# LoadCellAmplifier.net
KiCad netlist of a schematic drawn in Altium Designer
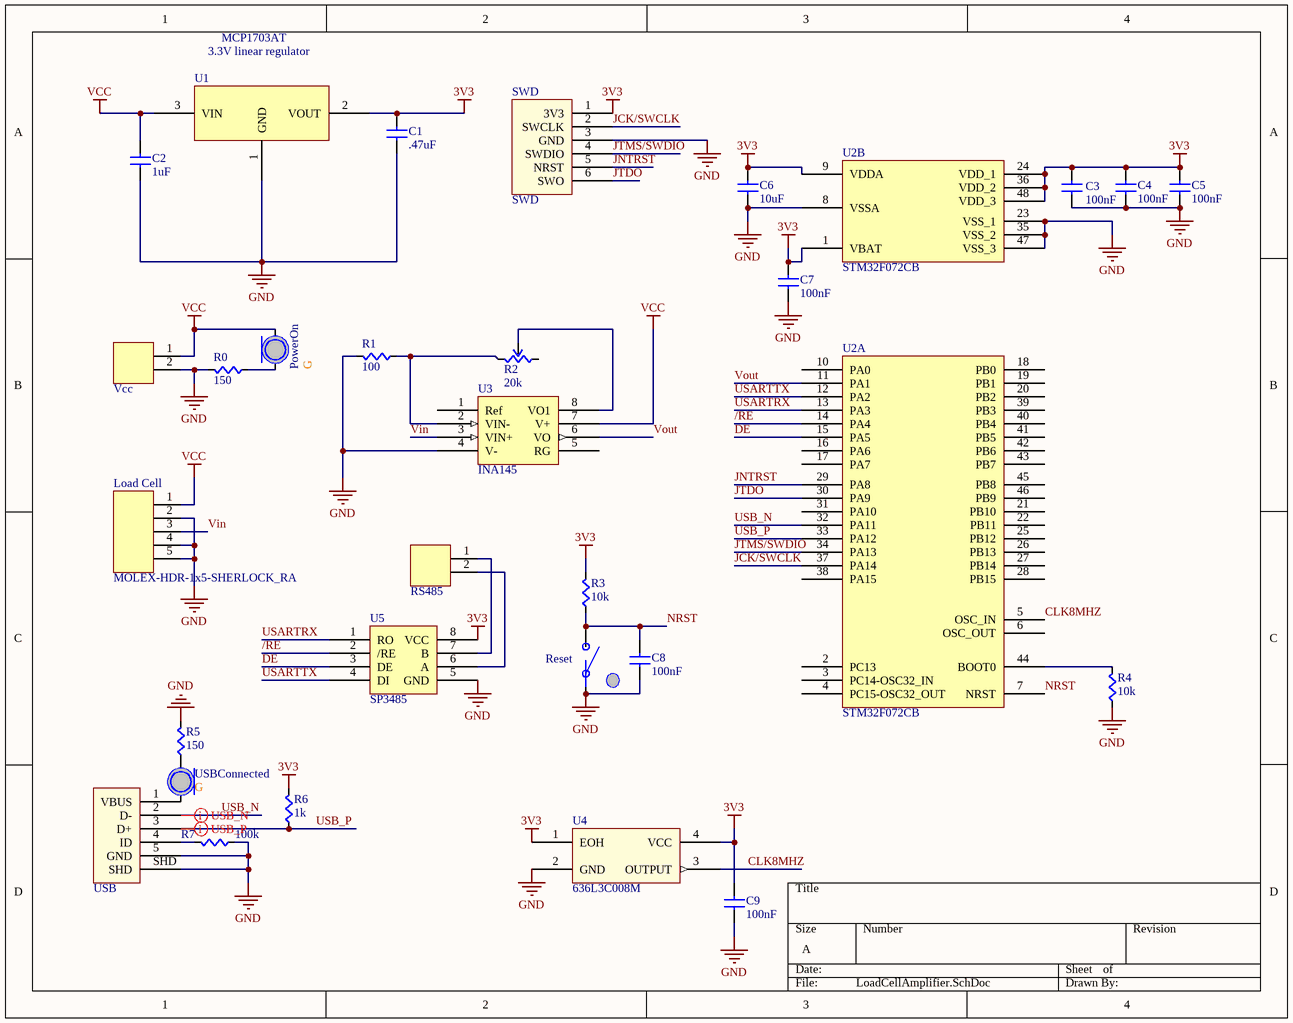
[diagram p0: LoadCellAmplifier.SchDoc]

(export (version "E")
  (design (tool "Eeschema 10.0.6"))
  (components
    (comp (ref "C1")
      (value ".47uF")
      (footprint "CAPC0603")
      (fields (field (name "Comment") "Cap"))
      (libsource (lib "SubjuGator8") (part "Cap"))
    )
    (comp (ref "C2")
      (value "1uF")
      (footprint "CAPC0603")
      (fields (field (name "Comment") "Cap"))
      (libsource (lib "SubjuGator8") (part "Cap"))
    )
    (comp (ref "C3")
      (value "100nF")
      (footprint "CAPC0603")
      (fields (field (name "Comment") "Cap"))
      (libsource (lib "SubjuGator8") (part "Cap"))
    )
    (comp (ref "C4")
      (value "100nF")
      (footprint "CAPC0603")
      (fields (field (name "Comment") "Cap"))
      (libsource (lib "SubjuGator8") (part "Cap"))
    )
    (comp (ref "C5")
      (value "100nF")
      (footprint "CAPC0603")
      (fields (field (name "Comment") "Cap"))
      (libsource (lib "SubjuGator8") (part "Cap"))
    )
    (comp (ref "C6")
      (value "10uF")
      (footprint "CAPC1206")
      (fields (field (name "Comment") "Cap"))
      (libsource (lib "SubjuGator8") (part "Cap"))
    )
    (comp (ref "C7")
      (value "100nF")
      (footprint "CAPC0603")
      (fields (field (name "Comment") "Cap"))
      (libsource (lib "SubjuGator8") (part "Cap"))
    )
    (comp (ref "C8")
      (value "100nF")
      (footprint "CAPC0603")
      (fields (field (name "Comment") "Cap"))
      (libsource (lib "SubjuGator8") (part "Cap"))
    )
    (comp (ref "C9")
      (value "100nF")
      (footprint "CAPC0603")
      (fields (field (name "Comment") "Cap"))
      (libsource (lib "SubjuGator8") (part "Cap"))
    )
    (comp (ref "Load Cell")
      (value "MOLEX-HDR-1x5-SHERLOCK_RA")
      (footprint "MOLEX-HDR-1X5-SHERLOCK- RA")
      (fields (field (name "MANUFACTURER PART NUMBER") "0353630560") (field (name "MANUFACTURER") "Molex"))
      (libsource (lib "Connectors") (part "MOLEX-HDR-1x5-SHERLOCK_RA"))
    )
    (comp (ref "PowerOn")
      (value "LED")
      (footprint "LED0805")
      (fields (field (name "COLOR") "G"))
      (libsource (lib "SubjuGator8") (part "LED"))
    )
    (comp (ref "R0")
      (value "150")
      (footprint "RES0603")
      (fields (field (name "Comment") "Res"))
      (libsource (lib "SubjuGator8") (part "Res"))
    )
    (comp (ref "R1")
      (value "100")
      (footprint "RES0603")
      (fields (field (name "Comment") "Res"))
      (libsource (lib "SubjuGator8") (part "Res"))
    )
    (comp (ref "R2")
      (value "20k")
      (footprint "ST4ETA103")
      (description "Potentiometer")
      (fields (field (name "Comment") "Pot"))
      (libsource (lib "SubjuGator8") (part "Potentiometer"))
    )
    (comp (ref "R3")
      (value "10k")
      (footprint "RES0603")
      (fields (field (name "Comment") "Res"))
      (libsource (lib "SubjuGator8") (part "Res"))
    )
    (comp (ref "R4")
      (value "10k")
      (footprint "RES0603")
      (fields (field (name "Comment") "Res"))
      (libsource (lib "SubjuGator8") (part "Res"))
    )
    (comp (ref "R5")
      (value "150")
      (footprint "RES0603")
      (fields (field (name "Comment") "Res"))
      (libsource (lib "SubjuGator8") (part "Res"))
    )
    (comp (ref "R6")
      (value "1k")
      (footprint "RES0603")
      (fields (field (name "Comment") "Res"))
      (libsource (lib "SubjuGator8") (part "Res"))
    )
    (comp (ref "R7")
      (value "100k")
      (footprint "RES0603")
      (fields (field (name "Comment") "Res"))
      (libsource (lib "SubjuGator8") (part "Res"))
    )
    (comp (ref "Reset")
      (value "Button")
      (footprint "PTS645xxxxSMTR92")
      (description "SPST Button")
      (libsource (lib "SubjuGator8") (part "Button"))
    )
    (comp (ref "RS485")
      (value "2-pin Horz Sherlock")
      (footprint "MOLEX-HDR-1X2-SHERLOCK-HORZ")
      (fields
        (field (name "MANUFACTURER PART NUMBER") "0353630260")
        (field (name "MANUFACTURER") "Molex Inc")
      )
      (libsource (lib "SubjuGator8") (part "MOLEX-HDR-1x2-SHERLOCK_RA"))
    )
    (comp (ref "SWD")
      (value "SWD")
      (footprint "SWD_STM32")
      (description "SWD connector matching the pinout on STM Discovery Boards")
      (libsource (lib "SubjuGator8") (part "SWD_STM32"))
    )
    (comp (ref "U1")
      (value "MCP1703AT")
      (footprint "MCP1703AT-xx02EMB")
      (description "250 mA, 16V, Low Quiescent Current LDO Regulator")
      (libsource (lib "SubjuGator8") (part "MCP1703AT"))
    )
    (comp (ref "U2")
      (value "STM32F072CB")
      (footprint "STM32F072CB")
      (description "MCU 32BIT 128KB FLASH 48LQFP")
      (libsource (lib "ICs") (part "STM32F072CB"))
    )
    (comp (ref "U3")
      (value "INA145")
      (footprint "INA145")
      (description "Diff Amp")
      (libsource (lib "PersonalLibrary") (part "INA145"))
    )
    (comp (ref "U4")
      (value "636L3C008M")
      (footprint "636L3C")
      (description "HCMOS/TTL Clock Oscillator")
      (libsource (lib "SubjuGator8") (part "636L3C"))
    )
    (comp (ref "U5")
      (value "SP3485")
      (footprint "SP3485")
      (description "IC TXRX RS485 HALF DUPLEX 8NSOIC")
      (libsource (lib "SubjuGator8") (part "SP3485"))
    )
    (comp (ref "USB")
      (value "USB Micro")
      (footprint "10118192-0001LF")
      (description "USB Mini B Metal Shield SMT")
      (libsource (lib "SubjuGator8") (part "USB Micro"))
    )
    (comp (ref "USBConnected")
      (value "LED")
      (footprint "LED0805")
      (fields (field (name "COLOR") "G"))
      (libsource (lib "") (part "LED_1"))
    )
    (comp (ref "Vcc")
      (value "2-pin Horz Sherlock")
      (footprint "MOLEX-HDR-1X2-SHERLOCK-HORZ")
      (fields
        (field (name "MANUFACTURER PART NUMBER") "0353630260")
        (field (name "MANUFACTURER") "Molex Inc")
      )
      (libsource (lib "Connectors") (part "MOLEX-HDR-1x2-SHERLOCK_RA"))
    )
  )
  (nets
    (net (code "1") (name "/CLK8MHZ") (class "Default")
      (node (ref "U2") (pin "5") (pinfunction "OSC_IN_5") (pintype "passive"))
      (node (ref "U4") (pin "3") (pinfunction "OUTPUT_3") (pintype "output"))
    )
    (net (code "2") (name "/DE") (class "Default")
      (node (ref "U2") (pin "15") (pinfunction "PA5_15") (pintype "passive"))
      (node (ref "U5") (pin "3") (pinfunction "DE_3") (pintype "passive"))
    )
    (net (code "3") (name "/JCK{slash}SWCLK") (class "Default")
      (node (ref "SWD") (pin "2") (pinfunction "SWCLK_2") (pintype "passive"))
      (node (ref "U2") (pin "37") (pinfunction "PA14_37") (pintype "passive"))
    )
    (net (code "4") (name "/JNTRST") (class "Default")
      (node (ref "SWD") (pin "5") (pinfunction "NRST_5") (pintype "passive"))
      (node (ref "U2") (pin "29") (pinfunction "PA8_29") (pintype "passive"))
    )
    (net (code "5") (name "/JTDO") (class "Default")
      (node (ref "SWD") (pin "6") (pinfunction "SWO_6") (pintype "passive"))
      (node (ref "U2") (pin "30") (pinfunction "PA9_30") (pintype "passive"))
    )
    (net (code "6") (name "/JTMS{slash}SWDIO") (class "Default")
      (node (ref "SWD") (pin "4") (pinfunction "SWDIO_4") (pintype "passive"))
      (node (ref "U2") (pin "34") (pinfunction "PA13_34") (pintype "passive"))
    )
    (net (code "7") (name "/NRST") (class "Default")
      (node (ref "C8") (pin "1") (pinfunction "A_1") (pintype "passive"))
      (node (ref "R3") (pin "2") (pinfunction "B_2") (pintype "passive"))
      (node (ref "Reset") (pin "B") (pinfunction "B_B") (pintype "passive"))
      (node (ref "U2") (pin "7") (pinfunction "NRST_7") (pintype "passive"))
    )
    (net (code "8") (name "/USARTRX") (class "Default")
      (node (ref "U2") (pin "13") (pinfunction "PA3_13") (pintype "passive"))
      (node (ref "U5") (pin "1") (pinfunction "RO_1") (pintype "passive"))
    )
    (net (code "9") (name "/USARTTX") (class "Default")
      (node (ref "U2") (pin "12") (pinfunction "PA2_12") (pintype "passive"))
      (node (ref "U5") (pin "4") (pinfunction "DI_4") (pintype "passive"))
    )
    (net (code "10") (name "/USB_N") (class "Default")
      (node (ref "U2") (pin "32") (pinfunction "PA11_32") (pintype "passive"))
      (node (ref "USB") (pin "2") (pinfunction "D-_2") (pintype "passive"))
    )
    (net (code "11") (name "/USB_P") (class "Default")
      (node (ref "R6") (pin "2") (pinfunction "B_2") (pintype "passive"))
      (node (ref "U2") (pin "33") (pinfunction "PA12_33") (pintype "passive"))
      (node (ref "USB") (pin "3") (pinfunction "D+_3") (pintype "passive"))
    )
    (net (code "12") (name "/Vin") (class "Default")
      (node (ref "Load Cell") (pin "3") (pinfunction "3_3") (pintype "passive"))
      (node (ref "U3") (pin "3") (pinfunction "VIN+_3") (pintype "input"))
    )
    (net (code "13") (name "/Vout") (class "Default")
      (node (ref "U2") (pin "11") (pinfunction "PA1_11") (pintype "passive"))
      (node (ref "U3") (pin "6") (pinfunction "VO_6") (pintype "output"))
    )
    (net (code "14") (name "/{slash}RE") (class "Default")
      (node (ref "U2") (pin "14") (pinfunction "PA4_14") (pintype "passive"))
      (node (ref "U5") (pin "2") (pinfunction "/RE_2") (pintype "passive"))
    )
    (net (code "15") (name "3V3") (class "Default")
      (node (ref "C1") (pin "1") (pinfunction "A_1") (pintype "passive"))
      (node (ref "C3") (pin "1") (pinfunction "A_1") (pintype "passive"))
      (node (ref "C4") (pin "1") (pinfunction "A_1") (pintype "passive"))
      (node (ref "C5") (pin "1") (pinfunction "A_1") (pintype "passive"))
      (node (ref "C6") (pin "2") (pinfunction "B_2") (pintype "passive"))
      (node (ref "C7") (pin "1") (pinfunction "A_1") (pintype "passive"))
      (node (ref "C9") (pin "1") (pinfunction "A_1") (pintype "passive"))
      (node (ref "R3") (pin "1") (pinfunction "A_1") (pintype "passive"))
      (node (ref "R6") (pin "1") (pinfunction "A_1") (pintype "passive"))
      (node (ref "SWD") (pin "1") (pinfunction "3V3_1") (pintype "passive"))
      (node (ref "U1") (pin "2") (pinfunction "VOUT_2") (pintype "passive"))
      (node (ref "U2") (pin "1") (pinfunction "VBAT_1") (pintype "passive"))
      (node (ref "U2") (pin "24") (pinfunction "VDD_1_24") (pintype "passive"))
      (node (ref "U2") (pin "36") (pinfunction "VDD_2_36") (pintype "passive"))
      (node (ref "U2") (pin "48") (pinfunction "VDD_3_48") (pintype "passive"))
      (node (ref "U2") (pin "9") (pinfunction "VDDA_9") (pintype "passive"))
      (node (ref "U4") (pin "1") (pinfunction "EOH_1") (pintype "passive"))
      (node (ref "U4") (pin "4") (pinfunction "VCC_4") (pintype "power_in"))
      (node (ref "U5") (pin "8") (pinfunction "VCC_8") (pintype "passive"))
    )
    (net (code "16") (name "GND") (class "Default")
      (node (ref "C1") (pin "2") (pinfunction "B_2") (pintype "passive"))
      (node (ref "C2") (pin "2") (pinfunction "B_2") (pintype "passive"))
      (node (ref "C3") (pin "2") (pinfunction "B_2") (pintype "passive"))
      (node (ref "C4") (pin "2") (pinfunction "B_2") (pintype "passive"))
      (node (ref "C5") (pin "2") (pinfunction "B_2") (pintype "passive"))
      (node (ref "C6") (pin "1") (pinfunction "A_1") (pintype "passive"))
      (node (ref "C7") (pin "2") (pinfunction "B_2") (pintype "passive"))
      (node (ref "C8") (pin "2") (pinfunction "B_2") (pintype "passive"))
      (node (ref "C9") (pin "2") (pinfunction "B_2") (pintype "passive"))
      (node (ref "Load Cell") (pin "2") (pinfunction "2_2") (pintype "passive"))
      (node (ref "Load Cell") (pin "4") (pinfunction "4_4") (pintype "passive"))
      (node (ref "Load Cell") (pin "5") (pinfunction "5_5") (pintype "passive"))
      (node (ref "R0") (pin "1") (pinfunction "A_1") (pintype "passive"))
      (node (ref "R1") (pin "1") (pinfunction "A_1") (pintype "passive"))
      (node (ref "R4") (pin "2") (pinfunction "B_2") (pintype "passive"))
      (node (ref "R5") (pin "1") (pinfunction "A_1") (pintype "passive"))
      (node (ref "R7") (pin "2") (pinfunction "B_2") (pintype "passive"))
      (node (ref "Reset") (pin "A") (pinfunction "A_A") (pintype "passive"))
      (node (ref "SWD") (pin "3") (pinfunction "GND_3") (pintype "passive"))
      (node (ref "U1") (pin "1") (pinfunction "GND_1") (pintype "power_in"))
      (node (ref "U2") (pin "23") (pinfunction "VSS_1_23") (pintype "passive"))
      (node (ref "U2") (pin "35") (pinfunction "VSS_2_35") (pintype "passive"))
      (node (ref "U2") (pin "47") (pinfunction "VSS_3_47") (pintype "passive"))
      (node (ref "U2") (pin "8") (pinfunction "VSSA_8") (pintype "passive"))
      (node (ref "U3") (pin "4") (pinfunction "V-_4") (pintype "passive"))
      (node (ref "U4") (pin "2") (pinfunction "GND_2") (pintype "power_in"))
      (node (ref "U5") (pin "5") (pinfunction "GND_5") (pintype "passive"))
      (node (ref "USB") (pin "5") (pinfunction "GND_5") (pintype "passive"))
      (node (ref "USB") (pin "SHD") (pinfunction "SHD_SHD") (pintype "passive"))
      (node (ref "Vcc") (pin "2") (pinfunction "2_2") (pintype "passive"))
    )
    (net (code "17") (name "Net-(R0-B)") (class "Default")
      (node (ref "PowerOn") (pin "C") (pinfunction "C_C") (pintype "passive"))
      (node (ref "R0") (pin "2") (pinfunction "B_2") (pintype "passive"))
    )
    (net (code "18") (name "Net-(R1-B)") (class "Default")
      (node (ref "R1") (pin "2") (pinfunction "B_2") (pintype "passive"))
      (node (ref "R2") (pin "1") (pinfunction "1_1") (pintype "passive"))
      (node (ref "U3") (pin "2") (pinfunction "VIN-_2") (pintype "input"))
    )
    (net (code "19") (name "Net-(R4-A)") (class "Default")
      (node (ref "R4") (pin "1") (pinfunction "A_1") (pintype "passive"))
      (node (ref "U2") (pin "44") (pinfunction "BOOT0_44") (pintype "passive"))
    )
    (net (code "20") (name "Net-(R5-B)") (class "Default")
      (node (ref "R5") (pin "2") (pinfunction "B_2") (pintype "passive"))
      (node (ref "USBConnected") (pin "C") (pinfunction "C_C") (pintype "passive"))
    )
    (net (code "21") (name "Net-(R7-A)") (class "Default")
      (node (ref "R7") (pin "1") (pinfunction "A_1") (pintype "passive"))
      (node (ref "USB") (pin "4") (pinfunction "ID_4") (pintype "passive"))
    )
    (net (code "22") (name "Net-(U3-VO1)") (class "Default")
      (node (ref "R2") (pin "3") (pinfunction "3_3") (pintype "passive"))
      (node (ref "U3") (pin "8") (pinfunction "VO1_8") (pintype "passive"))
    )
    (net (code "23") (name "Net-(U5-A)") (class "Default")
      (node (ref "RS485") (pin "2") (pinfunction "2_2") (pintype "passive"))
      (node (ref "U5") (pin "6") (pinfunction "A_6") (pintype "passive"))
    )
    (net (code "24") (name "Net-(U5-B)") (class "Default")
      (node (ref "RS485") (pin "1") (pinfunction "1_1") (pintype "passive"))
      (node (ref "U5") (pin "7") (pinfunction "B_7") (pintype "passive"))
    )
    (net (code "25") (name "Net-(USB-VBUS)") (class "Default")
      (node (ref "USB") (pin "1") (pinfunction "VBUS_1") (pintype "passive"))
      (node (ref "USBConnected") (pin "A") (pinfunction "A_A") (pintype "passive"))
    )
    (net (code "26") (name "VCC") (class "Default")
      (node (ref "C2") (pin "1") (pinfunction "A_1") (pintype "passive"))
      (node (ref "Load Cell") (pin "1") (pinfunction "1_1") (pintype "passive"))
      (node (ref "PowerOn") (pin "A") (pinfunction "A_A") (pintype "passive"))
      (node (ref "U1") (pin "3") (pinfunction "VIN_3") (pintype "passive"))
      (node (ref "U3") (pin "7") (pinfunction "V+_7") (pintype "passive"))
      (node (ref "Vcc") (pin "1") (pinfunction "1_1") (pintype "passive"))
    )
    (net (code "27") (name "unconnected-(R2-Pad2)") (class "Default")
      (node (ref "R2") (pin "2") (pinfunction "2_2") (pintype "passive"))
    )
    (net (code "28") (name "unconnected-(U2A-OSC_OUT-Pad6)") (class "Default")
      (node (ref "U2") (pin "6") (pinfunction "OSC_OUT_6") (pintype "passive"))
    )
    (net (code "29") (name "unconnected-(U2A-PA0-Pad10)") (class "Default")
      (node (ref "U2") (pin "10") (pinfunction "PA0_10") (pintype "passive"))
    )
    (net (code "30") (name "unconnected-(U2A-PA6-Pad16)") (class "Default")
      (node (ref "U2") (pin "16") (pinfunction "PA6_16") (pintype "passive"))
    )
    (net (code "31") (name "unconnected-(U2A-PA7-Pad17)") (class "Default")
      (node (ref "U2") (pin "17") (pinfunction "PA7_17") (pintype "passive"))
    )
    (net (code "32") (name "unconnected-(U2A-PA10-Pad31)") (class "Default")
      (node (ref "U2") (pin "31") (pinfunction "PA10_31") (pintype "passive"))
    )
    (net (code "33") (name "unconnected-(U2A-PA15-Pad38)") (class "Default")
      (node (ref "U2") (pin "38") (pinfunction "PA15_38") (pintype "passive"))
    )
    (net (code "34") (name "unconnected-(U2A-PB0-Pad18)") (class "Default")
      (node (ref "U2") (pin "18") (pinfunction "PB0_18") (pintype "passive"))
    )
    (net (code "35") (name "unconnected-(U2A-PB1-Pad19)") (class "Default")
      (node (ref "U2") (pin "19") (pinfunction "PB1_19") (pintype "passive"))
    )
    (net (code "36") (name "unconnected-(U2A-PB2-Pad20)") (class "Default")
      (node (ref "U2") (pin "20") (pinfunction "PB2_20") (pintype "passive"))
    )
    (net (code "37") (name "unconnected-(U2A-PB3-Pad39)") (class "Default")
      (node (ref "U2") (pin "39") (pinfunction "PB3_39") (pintype "passive"))
    )
    (net (code "38") (name "unconnected-(U2A-PB4-Pad40)") (class "Default")
      (node (ref "U2") (pin "40") (pinfunction "PB4_40") (pintype "passive"))
    )
    (net (code "39") (name "unconnected-(U2A-PB5-Pad41)") (class "Default")
      (node (ref "U2") (pin "41") (pinfunction "PB5_41") (pintype "passive"))
    )
    (net (code "40") (name "unconnected-(U2A-PB6-Pad42)") (class "Default")
      (node (ref "U2") (pin "42") (pinfunction "PB6_42") (pintype "passive"))
    )
    (net (code "41") (name "unconnected-(U2A-PB7-Pad43)") (class "Default")
      (node (ref "U2") (pin "43") (pinfunction "PB7_43") (pintype "passive"))
    )
    (net (code "42") (name "unconnected-(U2A-PB8-Pad45)") (class "Default")
      (node (ref "U2") (pin "45") (pinfunction "PB8_45") (pintype "passive"))
    )
    (net (code "43") (name "unconnected-(U2A-PB9-Pad46)") (class "Default")
      (node (ref "U2") (pin "46") (pinfunction "PB9_46") (pintype "passive"))
    )
    (net (code "44") (name "unconnected-(U2A-PB10-Pad21)") (class "Default")
      (node (ref "U2") (pin "21") (pinfunction "PB10_21") (pintype "passive"))
    )
    (net (code "45") (name "unconnected-(U2A-PB11-Pad22)") (class "Default")
      (node (ref "U2") (pin "22") (pinfunction "PB11_22") (pintype "passive"))
    )
    (net (code "46") (name "unconnected-(U2A-PB12-Pad25)") (class "Default")
      (node (ref "U2") (pin "25") (pinfunction "PB12_25") (pintype "passive"))
    )
    (net (code "47") (name "unconnected-(U2A-PB13-Pad26)") (class "Default")
      (node (ref "U2") (pin "26") (pinfunction "PB13_26") (pintype "passive"))
    )
    (net (code "48") (name "unconnected-(U2A-PB14-Pad27)") (class "Default")
      (node (ref "U2") (pin "27") (pinfunction "PB14_27") (pintype "passive"))
    )
    (net (code "49") (name "unconnected-(U2A-PB15-Pad28)") (class "Default")
      (node (ref "U2") (pin "28") (pinfunction "PB15_28") (pintype "passive"))
    )
    (net (code "50") (name "unconnected-(U2A-PC13-Pad2)") (class "Default")
      (node (ref "U2") (pin "2") (pinfunction "PC13_2") (pintype "passive"))
    )
    (net (code "51") (name "unconnected-(U2A-PC14-OSC32_IN-Pad3)") (class "Default")
      (node (ref "U2") (pin "3") (pinfunction "PC14-OSC32_IN_3") (pintype "passive"))
    )
    (net (code "52") (name "unconnected-(U2A-PC15-OSC32_OUT-Pad4)") (class "Default")
      (node (ref "U2") (pin "4") (pinfunction "PC15-OSC32_OUT_4") (pintype "passive"))
    )
    (net (code "53") (name "unconnected-(U3-RG-Pad5)") (class "Default")
      (node (ref "U3") (pin "5") (pinfunction "RG_5") (pintype "passive"))
    )
    (net (code "54") (name "unconnected-(U3-Ref-Pad1)") (class "Default")
      (node (ref "U3") (pin "1") (pinfunction "Ref_1") (pintype "passive"))
    )
  )
)
